# BG95_VLT.net
KiCad netlist of a schematic drawn in Altium Designer
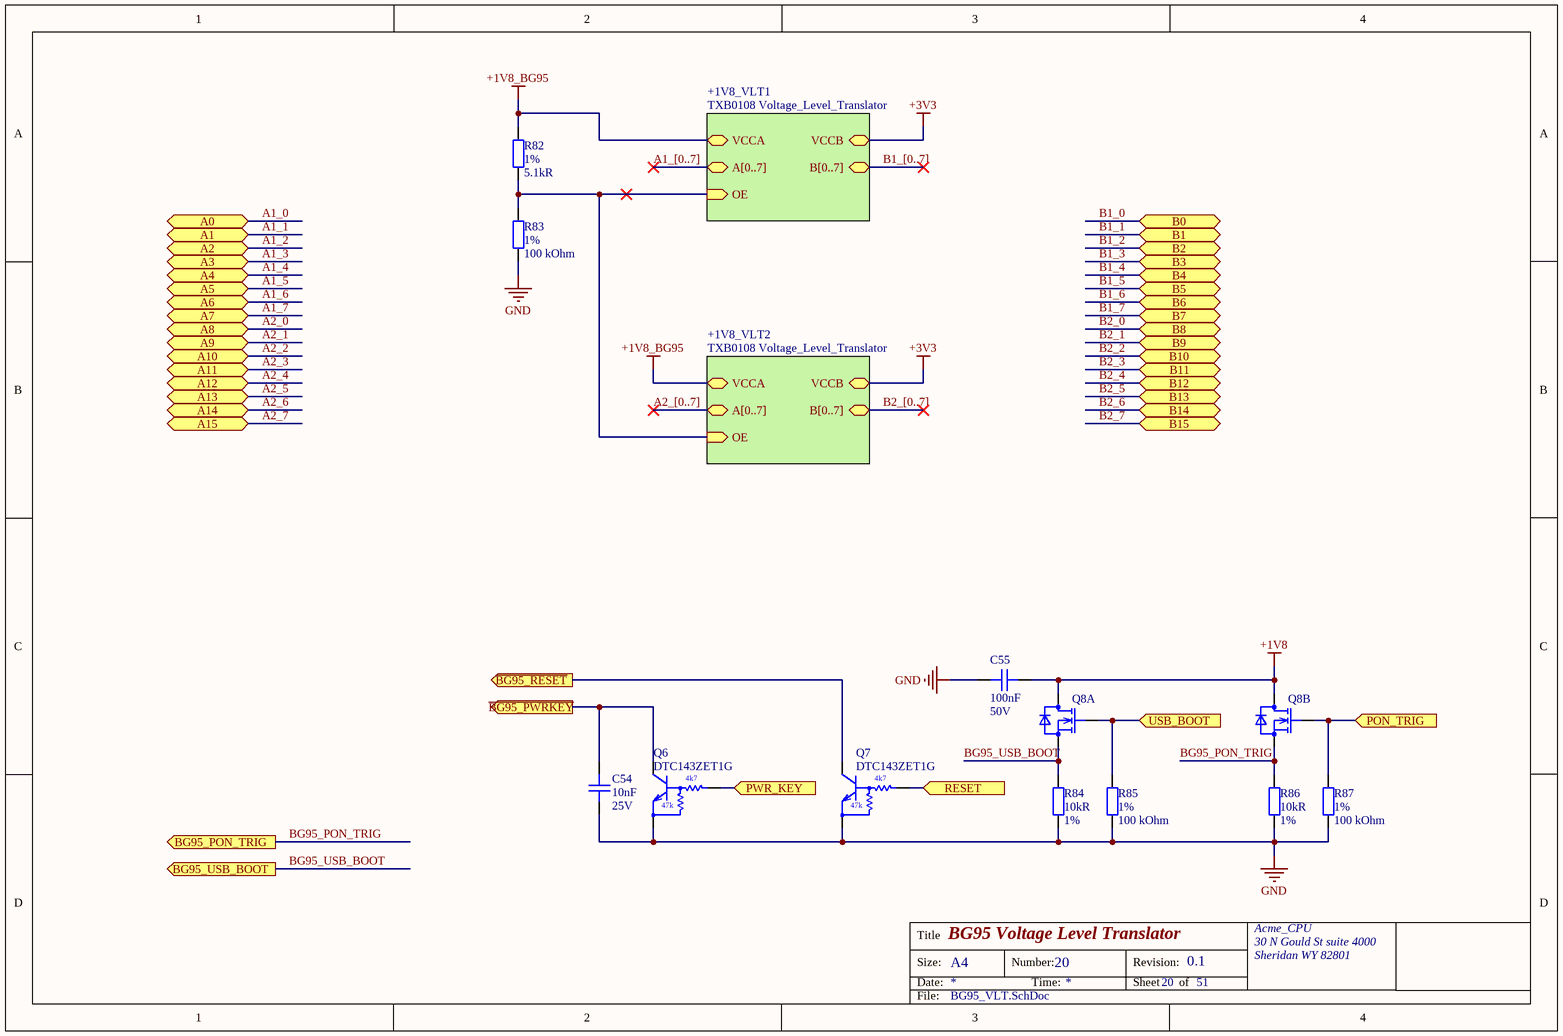
[diagram p0: BG95_VLT.SchDoc]

(export (version "E")
  (design (tool "Eeschema 10.0.6"))
  (components
    (comp (ref "C54")
      (value "CAP CER 10nF 25V X7R 10% 0402")
      (footprint "C0402")
      (description "Cap Cer 10nF 25V X7R 10% 0402")
      (fields
        (field (name "MANUFACTURER") "Kyocera AVX")
        (field (name "MANUFACTURER PART NUMBER") "04023C103KAT2A")
        (field (name "CAPACITANCE") "10nF")
        (field (name "VOLTAGE") "25V")
      )
      (libsource (lib "capacitors_smd") (part "CAP CER 10nF 25V X7R 10% 0402"))
    )
    (comp (ref "C55")
      (value "CAP CER 0.1UF 50V X7R 0402")
      (footprint "C0402")
      (description "0.1µF ±10% 50V Ceramic Capacitor X7R 0402 (1005 Metric)")
      (fields
        (field (name "MANUFACTURER") "TDK")
        (field (name "MANUFACTURER PART NUMBER") "CGA2B3X7R1H104K050BB")
        (field (name "CAPACITANCE") "100nF")
        (field (name "VOLTAGE") "50V")
      )
      (libsource (lib "capacitors_smd") (part "CAP CER 0.1UF 50V X7R 0402"))
    )
    (comp (ref "Q6")
      (value "DTC143ZET1G")
      (footprint "SOT-416FL_ONS")
      (description "Pre-Biased Bipolar Transistor (BJT) NPN - Pre-Biased 50V 100mA  200mW Surface Mount SC-75, SOT-416")
      (fields (field (name "MANUFACTURER") "ON Semiconductor"))
      (libsource (lib "bipolar-junction_transistors_pre_biased") (part "TRANS PREBIAS NPN 200MW SC75"))
    )
    (comp (ref "Q7")
      (value "DTC143ZET1G")
      (footprint "SOT-416FL_ONS")
      (description "Pre-Biased Bipolar Transistor (BJT) NPN - Pre-Biased 50V 100mA  200mW Surface Mount SC-75, SOT-416")
      (fields (field (name "MANUFACTURER") "ON Semiconductor"))
      (libsource (lib "bipolar-junction_transistors_pre_biased") (part "TRANS PREBIAS NPN 200MW SC75"))
    )
    (comp (ref "Q8")
      (value "DMN32D2LV-7")
      (footprint "SON_400UV-7_DIO")
      (description "Mosfet Array 2 N-Channel (Dual) 30V 400mA 400mW Surface Mount SOT-563")
      (fields (field (name "MANUFACTURER") "Diodes"))
      (libsource (lib "mosfets") (part "ARRAY MOSFET 2N-CH 30V 0.4A SOT-563"))
    )
    (comp (ref "R82")
      (value "RES SMD 5.1K OHM 1% 1/16W 0402")
      (footprint "R0402")
      (description "5.1 kOhms ±1% 0.063W, 1/16W Chip Resistor 0402 (1005 Metric) Moisture Resistant Thick Film")
      (fields
        (field (name "MANUFACTURER") "Yageo")
        (field (name "MANUFACTURER PART NUMBER") "RC0402FR-075K1L")
        (field (name "TOLERANCE") "1%")
        (field (name "RESISTANCE") "5.1kR")
      )
      (libsource (lib "resistors_smd") (part "RES SMD 5.1K OHM 1% 1/16W 0402"))
    )
    (comp (ref "R83")
      (value "RES SMD 100K OHM 1% 1/16W 0402")
      (footprint "R0402")
      (description "100 kOhms ±1% 0.063W, 1/16W Chip Resistor 0402 (1005 Metric) Moisture Resistant Thick Film")
      (fields
        (field (name "MANUFACTURER") "Yageo")
        (field (name "MANUFACTURER PART NUMBER") "RC0402FR-07100KL")
        (field (name "TOLERANCE") "1%")
        (field (name "RESISTANCE") "100 kOhm")
      )
      (libsource (lib "resistors_smd") (part "RES SMD 100K OHM 1% 1/16W 0402"))
    )
    (comp (ref "R84")
      (value "RES SMD 10K OHM 1% 1/16W 0402")
      (footprint "R0402")
      (description "10 kOhms ±1% 0.063W, 1/16W Chip Resistor 0402 (1005 Metric) Moisture Resistant Thick Film")
      (fields
        (field (name "MANUFACTURER") "Yageo")
        (field (name "MANUFACTURER PART NUMBER") "RC0402FR-0710KP")
        (field (name "RESISTANCE") "10kR")
        (field (name "TOLERANCE") "1%")
      )
      (libsource (lib "resistors_smd") (part "RES SMD 10K OHM 1% 1/16W 0402"))
    )
    (comp (ref "R85")
      (value "RES SMD 100K OHM 1% 1/16W 0402")
      (footprint "R0402")
      (description "100 kOhms ±1% 0.063W, 1/16W Chip Resistor 0402 (1005 Metric) Moisture Resistant Thick Film")
      (fields
        (field (name "MANUFACTURER") "Yageo")
        (field (name "MANUFACTURER PART NUMBER") "RC0402FR-07100KL")
        (field (name "TOLERANCE") "1%")
        (field (name "RESISTANCE") "100 kOhm")
      )
      (libsource (lib "resistors_smd") (part "RES SMD 100K OHM 1% 1/16W 0402"))
    )
    (comp (ref "R86")
      (value "RES SMD 10K OHM 1% 1/16W 0402")
      (footprint "R0402")
      (description "10 kOhms ±1% 0.063W, 1/16W Chip Resistor 0402 (1005 Metric) Moisture Resistant Thick Film")
      (fields
        (field (name "MANUFACTURER") "Yageo")
        (field (name "MANUFACTURER PART NUMBER") "RC0402FR-0710KP")
        (field (name "RESISTANCE") "10kR")
        (field (name "TOLERANCE") "1%")
      )
      (libsource (lib "resistors_smd") (part "RES SMD 10K OHM 1% 1/16W 0402"))
    )
    (comp (ref "R87")
      (value "RES SMD 100K OHM 1% 1/16W 0402")
      (footprint "R0402")
      (description "100 kOhms ±1% 0.063W, 1/16W Chip Resistor 0402 (1005 Metric) Moisture Resistant Thick Film")
      (fields
        (field (name "MANUFACTURER") "Yageo")
        (field (name "MANUFACTURER PART NUMBER") "RC0402FR-07100KL")
        (field (name "TOLERANCE") "1%")
        (field (name "RESISTANCE") "100 kOhm")
      )
      (libsource (lib "resistors_smd") (part "RES SMD 100K OHM 1% 1/16W 0402"))
    )
  )
  (nets
    (net (code "1") (name "+1V8") (class "Default")
      (node (ref "C55") (pin "2") (pinfunction "2_2") (pintype "passive"))
      (node (ref "Q8") (pin "3") (pinfunction "D_3") (pintype "passive"))
      (node (ref "Q8") (pin "6") (pinfunction "D_6") (pintype "passive"))
    )
    (net (code "2") (name "+1V8_BG95") (class "Default")
      (node (ref "R82") (pin "1") (pinfunction "1_1") (pintype "passive"))
    )
    (net (code "40") (name "/BG95_PON_TRIG") (class "Default")
      (node (ref "Q8") (pin "4") (pinfunction "S_4") (pintype "passive"))
      (node (ref "R86") (pin "1") (pinfunction "1_1") (pintype "passive"))
    )
    (net (code "41") (name "/BG95_PWRKEY") (class "Default")
      (node (ref "C54") (pin "2") (pinfunction "2_2") (pintype "passive"))
      (node (ref "Q6") (pin "3") (pinfunction "C_3") (pintype "passive"))
    )
    (net (code "42") (name "/BG95_RESET") (class "Default")
      (node (ref "Q7") (pin "3") (pinfunction "C_3") (pintype "passive"))
    )
    (net (code "43") (name "/BG95_USB_BOOT") (class "Default")
      (node (ref "Q8") (pin "1") (pinfunction "S_1") (pintype "passive"))
      (node (ref "R84") (pin "1") (pinfunction "1_1") (pintype "passive"))
    )
    (net (code "44") (name "/OE") (class "Default")
      (node (ref "R82") (pin "2") (pinfunction "2_2") (pintype "passive"))
      (node (ref "R83") (pin "2") (pinfunction "2_2") (pintype "passive"))
    )
    (net (code "45") (name "/PON_TRIG") (class "Default")
      (node (ref "Q8") (pin "5") (pinfunction "G_5") (pintype "passive"))
      (node (ref "R87") (pin "2") (pinfunction "2_2") (pintype "passive"))
    )
    (net (code "46") (name "/PWR_KEY") (class "Default")
      (node (ref "Q6") (pin "1") (pinfunction "B_1") (pintype "passive"))
    )
    (net (code "47") (name "/RESET") (class "Default")
      (node (ref "Q7") (pin "1") (pinfunction "B_1") (pintype "passive"))
    )
    (net (code "48") (name "/USB_BOOT") (class "Default")
      (node (ref "Q8") (pin "2") (pinfunction "G_2") (pintype "passive"))
      (node (ref "R85") (pin "2") (pinfunction "2_2") (pintype "passive"))
    )
    (net (code "49") (name "GND") (class "Default")
      (node (ref "C54") (pin "1") (pinfunction "1_1") (pintype "passive"))
      (node (ref "C55") (pin "1") (pinfunction "1_1") (pintype "passive"))
      (node (ref "Q6") (pin "2") (pinfunction "E_2") (pintype "passive"))
      (node (ref "Q7") (pin "2") (pinfunction "E_2") (pintype "passive"))
      (node (ref "R83") (pin "1") (pinfunction "1_1") (pintype "passive"))
      (node (ref "R84") (pin "2") (pinfunction "2_2") (pintype "passive"))
      (node (ref "R85") (pin "1") (pinfunction "1_1") (pintype "passive"))
      (node (ref "R86") (pin "2") (pinfunction "2_2") (pintype "passive"))
      (node (ref "R87") (pin "1") (pinfunction "1_1") (pintype "passive"))
    )
  )
)
